# PLL.net
KiCad netlist of a schematic drawn in Altium Designer
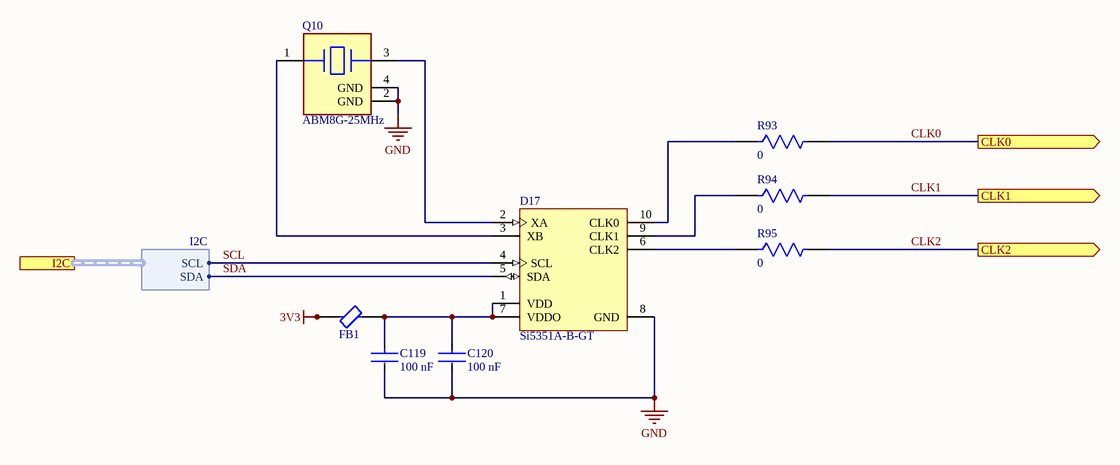
[diagram p0: PLL.SchDoc]

(export (version "E")
  (design (tool "Eeschema 10.0.6"))
  (components
    (comp (ref "C119")
      (value "CC0805-1.5pF")
      (footprint "CC0805")
      (description "CL21 Series 0805 1.5pF 50V ±0.25pF Tolerance C0G Multilayer Ceramic Chip Capacitor")
      (fields
        (field (name "MANUFACTURER PART NUMBER") "CL21C1R5CBANNNC")
        (field (name "MANUFACTURER") "Samsung")
        (field (name "CAPACITANCE") "100 nF")
      )
      (libsource (lib "zxevo") (part "CC0805"))
    )
    (comp (ref "C120")
      (value "CC0805-1.5pF")
      (footprint "CC0805")
      (description "CL21 Series 0805 1.5pF 50V ±0.25pF Tolerance C0G Multilayer Ceramic Chip Capacitor")
      (fields
        (field (name "MANUFACTURER PART NUMBER") "CL21C1R5CBANNNC")
        (field (name "MANUFACTURER") "Samsung")
        (field (name "CAPACITANCE") "100 nF")
      )
      (libsource (lib "zxevo") (part "CC0805"))
    )
    (comp (ref "D17")
      (value "Si5351A-B-GT")
      (footprint "SLAB-MSOP-10_L")
      (fields
        (field (name "MANUFACTURER") "Silicon Labs")
        (field (name "MANUFACTURER PART NUMBER") "SI5351A-B-GT")
      )
      (libsource (lib "zxevo") (part "Si5351A-B-GT"))
    )
    (comp (ref "FB1")
      (value "BLM21AG601SN1J")
      (footprint "FP-BLM21-0_2-t0_85-e0_5-IPC_A")
      (description "Chip Ferrite Bead, 0805, 600Ω @ 100MHz, 0.2Ω, 25%, 700mA")
      (fields (field (name "MANUFACTURER") "Murata"))
      (libsource (lib "zxevo") (part "BLM21AG601SN1J"))
    )
    (comp (ref "Q10")
      (value "ABM8G-25MHz")
      (footprint "FP-ABM8G-MFG")
      (description "CRYSTAL 25.0000MHZ 10PF SMD")
      (fields
        (field (name "MANUFACTURER") "Abracon")
        (field (name "MANUFACTURER PART NUMBER") "ABM8G-25.000MHZ-B4Y-T")
      )
      (libsource (lib "zxevo") (part "ABM8G-25MHz"))
    )
    (comp (ref "R93")
      (value "CR0805-51")
      (footprint "CR0805")
      (description "51Ω ±0.5% 0.1W 1/10W Chip Resistor 0805 (2012 Metric) Thin Film")
      (fields
        (field (name "RESISTANCE") "0")
        (field (name "MANUFACTURER") "Susumu")
        (field (name "MANUFACTURER PART NUMBER") "RR1220Q-510-D")
      )
      (libsource (lib "zxevo") (part "CR0805"))
    )
    (comp (ref "R94")
      (value "CR0805-51")
      (footprint "CR0805")
      (description "51Ω ±0.5% 0.1W 1/10W Chip Resistor 0805 (2012 Metric) Thin Film")
      (fields
        (field (name "RESISTANCE") "0")
        (field (name "MANUFACTURER") "Susumu")
        (field (name "MANUFACTURER PART NUMBER") "RR1220Q-510-D")
      )
      (libsource (lib "zxevo") (part "CR0805"))
    )
    (comp (ref "R95")
      (value "CR0805-51")
      (footprint "CR0805")
      (description "51Ω ±0.5% 0.1W 1/10W Chip Resistor 0805 (2012 Metric) Thin Film")
      (fields
        (field (name "RESISTANCE") "0")
        (field (name "MANUFACTURER") "Susumu")
        (field (name "MANUFACTURER PART NUMBER") "RR1220Q-510-D")
      )
      (libsource (lib "zxevo") (part "CR0805"))
    )
  )
  (nets
    (net (code "2") (name "/CLK0") (class "Default")
      (node (ref "R93") (pin "2") (pinfunction "2_2") (pintype "passive"))
    )
    (net (code "3") (name "/CLK1") (class "Default")
      (node (ref "R94") (pin "2") (pinfunction "2_2") (pintype "passive"))
    )
    (net (code "4") (name "/CLK2") (class "Default")
      (node (ref "R95") (pin "2") (pinfunction "2_2") (pintype "passive"))
    )
    (net (code "5") (name "/SCL") (class "Default")
      (node (ref "D17") (pin "4") (pinfunction "SCL_4") (pintype "input"))
    )
    (net (code "6") (name "/SDA") (class "Default")
      (node (ref "D17") (pin "5") (pinfunction "SDA_5") (pintype "bidirectional"))
    )
    (net (code "8") (name "3V3") (class "Default")
      (node (ref "FB1") (pin "1") (pinfunction "1_1") (pintype "passive"))
    )
    (net (code "9") (name "GND") (class "Default")
      (node (ref "C119") (pin "2") (pinfunction "2_2") (pintype "passive"))
      (node (ref "C120") (pin "2") (pinfunction "2_2") (pintype "passive"))
      (node (ref "D17") (pin "8") (pinfunction "GND_8") (pintype "power_in"))
      (node (ref "Q10") (pin "2") (pinfunction "GND_2") (pintype "power_in"))
      (node (ref "Q10") (pin "4") (pinfunction "GND_4") (pintype "power_in"))
    )
    (net (code "10") (name "Net-(D17-CLK0)") (class "Default")
      (node (ref "D17") (pin "10") (pinfunction "CLK0_10") (pintype "tri_state"))
      (node (ref "R93") (pin "1") (pinfunction "1_1") (pintype "passive"))
    )
    (net (code "11") (name "Net-(D17-CLK1)") (class "Default")
      (node (ref "D17") (pin "9") (pinfunction "CLK1_9") (pintype "tri_state"))
      (node (ref "R94") (pin "1") (pinfunction "1_1") (pintype "passive"))
    )
    (net (code "12") (name "Net-(D17-CLK2)") (class "Default")
      (node (ref "D17") (pin "6") (pinfunction "CLK2_6") (pintype "tri_state"))
      (node (ref "R95") (pin "1") (pinfunction "1_1") (pintype "passive"))
    )
    (net (code "13") (name "Net-(D17-VDD)") (class "Default")
      (node (ref "C119") (pin "1") (pinfunction "1_1") (pintype "passive"))
      (node (ref "C120") (pin "1") (pinfunction "1_1") (pintype "passive"))
      (node (ref "D17") (pin "1") (pinfunction "VDD_1") (pintype "power_in"))
      (node (ref "D17") (pin "7") (pinfunction "VDDO_7") (pintype "power_in"))
      (node (ref "FB1") (pin "2") (pinfunction "2_2") (pintype "passive"))
    )
    (net (code "14") (name "Net-(D17-XA)") (class "Default")
      (node (ref "D17") (pin "2") (pinfunction "XA_2") (pintype "input"))
      (node (ref "Q10") (pin "3") (pinfunction "3_3") (pintype "passive"))
    )
    (net (code "15") (name "Net-(D17-XB)") (class "Default")
      (node (ref "D17") (pin "3") (pinfunction "XB_3") (pintype "passive"))
      (node (ref "Q10") (pin "1") (pinfunction "1_1") (pintype "passive"))
    )
  )
)
